# IO_ctrl.net
KiCad netlist of a schematic drawn in Altium Designer
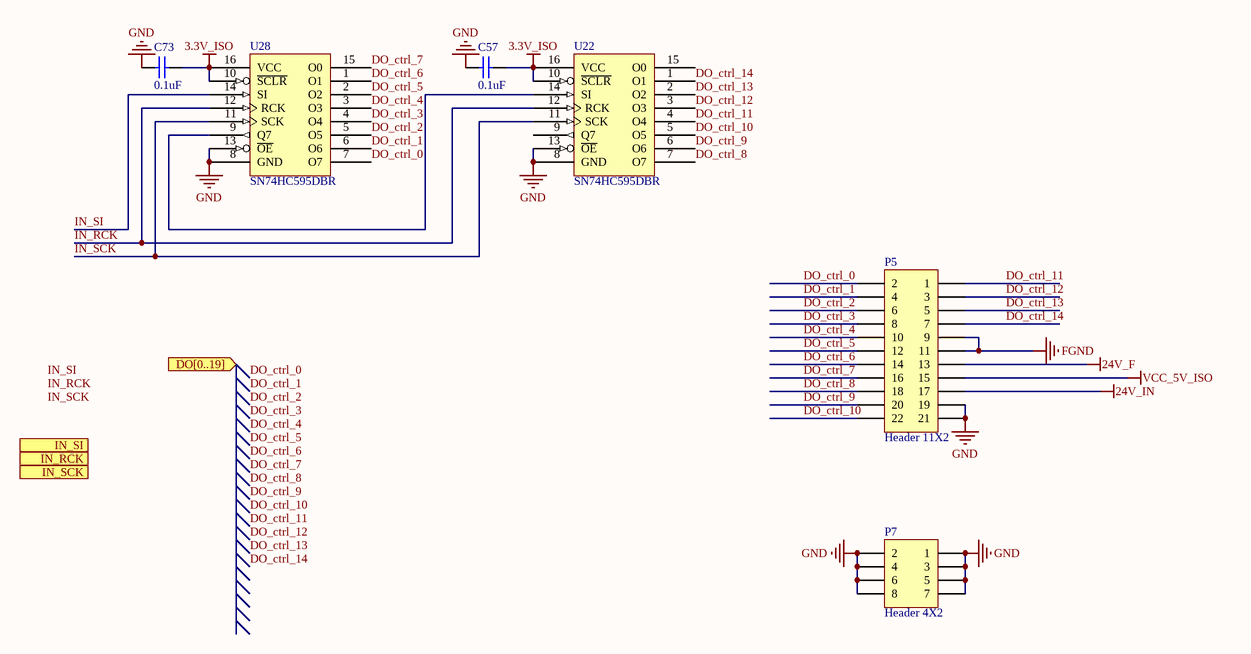
[diagram p0: IO_ctrl.SchDoc]

(export (version "E")
  (design (tool "Eeschema 10.0.6"))
  (components
    (comp (ref "C57")
      (value "0.1uF")
      (footprint "0603C")
      (description "Capacitor")
      (fields (field (name "PUBLISHER") "Altium Limited"))
      (libsource (lib "Miscellaneous Devices") (part "Cap"))
    )
    (comp (ref "C73")
      (value "0.1uF")
      (footprint "0603C")
      (description "Capacitor")
      (fields (field (name "PUBLISHER") "Altium Limited"))
      (libsource (lib "Miscellaneous Devices") (part "Cap"))
    )
    (comp (ref "P5")
      (value "Header 11X2")
      (footprint "HDR2X11")
      (description "Header, 11-Pin, Dual row")
      (fields (field (name "PUBLISHER") "Altium Limited"))
      (libsource (lib "Miscellaneous Connectors") (part "Header 11X2"))
    )
    (comp (ref "P7")
      (value "Header 4X2")
      (footprint "HDR2X4")
      (description "Header, 4-Pin, Dual row")
      (fields (field (name "PUBLISHER") "Altium Limited"))
      (libsource (lib "Miscellaneous Connectors") (part "Header 4X2"))
    )
    (comp (ref "U22") (value "SN74HC595DBR") (footprint "SSOP16") (libsource (lib "DI16") (part "74HC595")))
    (comp (ref "U28") (value "SN74HC595DBR") (footprint "SSOP16") (libsource (lib "DI16") (part "74HC595")))
  )
  (nets
    (net (code "22") (name "/DO_ctrl_0") (class "Default")
      (node (ref "P5") (pin "2") (pinfunction "2_2") (pintype "passive"))
      (node (ref "U28") (pin "7") (pinfunction "O7_7") (pintype "tri_state"))
    )
    (net (code "23") (name "/DO_ctrl_1") (class "Default")
      (node (ref "P5") (pin "4") (pinfunction "4_4") (pintype "passive"))
      (node (ref "U28") (pin "6") (pinfunction "O6_6") (pintype "tri_state"))
    )
    (net (code "24") (name "/DO_ctrl_2") (class "Default")
      (node (ref "P5") (pin "6") (pinfunction "6_6") (pintype "passive"))
      (node (ref "U28") (pin "5") (pinfunction "O5_5") (pintype "tri_state"))
    )
    (net (code "25") (name "/DO_ctrl_3") (class "Default")
      (node (ref "P5") (pin "8") (pinfunction "8_8") (pintype "passive"))
      (node (ref "U28") (pin "4") (pinfunction "O4_4") (pintype "tri_state"))
    )
    (net (code "26") (name "/DO_ctrl_4") (class "Default")
      (node (ref "P5") (pin "10") (pinfunction "10_10") (pintype "passive"))
      (node (ref "U28") (pin "3") (pinfunction "O3_3") (pintype "tri_state"))
    )
    (net (code "27") (name "/DO_ctrl_5") (class "Default")
      (node (ref "P5") (pin "12") (pinfunction "12_12") (pintype "passive"))
      (node (ref "U28") (pin "2") (pinfunction "O2_2") (pintype "tri_state"))
    )
    (net (code "28") (name "/DO_ctrl_6") (class "Default")
      (node (ref "P5") (pin "14") (pinfunction "14_14") (pintype "passive"))
      (node (ref "U28") (pin "1") (pinfunction "O1_1") (pintype "tri_state"))
    )
    (net (code "29") (name "/DO_ctrl_7") (class "Default")
      (node (ref "P5") (pin "16") (pinfunction "16_16") (pintype "passive"))
      (node (ref "U28") (pin "15") (pinfunction "O0_15") (pintype "tri_state"))
    )
    (net (code "30") (name "/DO_ctrl_8") (class "Default")
      (node (ref "P5") (pin "18") (pinfunction "18_18") (pintype "passive"))
      (node (ref "U22") (pin "7") (pinfunction "O7_7") (pintype "tri_state"))
    )
    (net (code "31") (name "/DO_ctrl_9") (class "Default")
      (node (ref "P5") (pin "20") (pinfunction "20_20") (pintype "passive"))
      (node (ref "U22") (pin "6") (pinfunction "O6_6") (pintype "tri_state"))
    )
    (net (code "32") (name "/DO_ctrl_10") (class "Default")
      (node (ref "P5") (pin "22") (pinfunction "22_22") (pintype "passive"))
      (node (ref "U22") (pin "5") (pinfunction "O5_5") (pintype "tri_state"))
    )
    (net (code "33") (name "/DO_ctrl_11") (class "Default")
      (node (ref "P5") (pin "1") (pinfunction "1_1") (pintype "passive"))
      (node (ref "U22") (pin "4") (pinfunction "O4_4") (pintype "tri_state"))
    )
    (net (code "34") (name "/DO_ctrl_12") (class "Default")
      (node (ref "P5") (pin "3") (pinfunction "3_3") (pintype "passive"))
      (node (ref "U22") (pin "3") (pinfunction "O3_3") (pintype "tri_state"))
    )
    (net (code "35") (name "/DO_ctrl_13") (class "Default")
      (node (ref "P5") (pin "5") (pinfunction "5_5") (pintype "passive"))
      (node (ref "U22") (pin "2") (pinfunction "O2_2") (pintype "tri_state"))
    )
    (net (code "36") (name "/DO_ctrl_14") (class "Default")
      (node (ref "P5") (pin "7") (pinfunction "7_7") (pintype "passive"))
      (node (ref "U22") (pin "1") (pinfunction "O1_1") (pintype "tri_state"))
    )
    (net (code "37") (name "/IN_RCK") (class "Default")
      (node (ref "U22") (pin "12") (pinfunction "RCK_12") (pintype "input"))
      (node (ref "U28") (pin "12") (pinfunction "RCK_12") (pintype "input"))
    )
    (net (code "38") (name "/IN_SCK") (class "Default")
      (node (ref "U22") (pin "11") (pinfunction "SCK_11") (pintype "input"))
      (node (ref "U28") (pin "11") (pinfunction "SCK_11") (pintype "input"))
    )
    (net (code "39") (name "/IN_SI") (class "Default")
      (node (ref "U28") (pin "14") (pinfunction "SI_14") (pintype "input"))
    )
    (net (code "40") (name "3.3V_ISO") (class "Default")
      (node (ref "C57") (pin "1") (pinfunction "1_1") (pintype "passive"))
      (node (ref "C73") (pin "1") (pinfunction "1_1") (pintype "passive"))
      (node (ref "U22") (pin "10") (pinfunction "~{SCLR}_10") (pintype "input"))
      (node (ref "U22") (pin "16") (pinfunction "VCC_16") (pintype "power_in"))
      (node (ref "U28") (pin "10") (pinfunction "~{SCLR}_10") (pintype "input"))
      (node (ref "U28") (pin "16") (pinfunction "VCC_16") (pintype "power_in"))
    )
    (net (code "41") (name "24V_F") (class "Default")
      (node (ref "P5") (pin "13") (pinfunction "13_13") (pintype "passive"))
    )
    (net (code "42") (name "24V_IN") (class "Default")
      (node (ref "P5") (pin "17") (pinfunction "17_17") (pintype "passive"))
    )
    (net (code "43") (name "FGND") (class "Default")
      (node (ref "P5") (pin "11") (pinfunction "11_11") (pintype "passive"))
      (node (ref "P5") (pin "9") (pinfunction "9_9") (pintype "passive"))
    )
    (net (code "44") (name "GND") (class "Default")
      (node (ref "C57") (pin "2") (pinfunction "2_2") (pintype "passive"))
      (node (ref "C73") (pin "2") (pinfunction "2_2") (pintype "passive"))
      (node (ref "P5") (pin "19") (pinfunction "19_19") (pintype "passive"))
      (node (ref "P5") (pin "21") (pinfunction "21_21") (pintype "passive"))
      (node (ref "P7") (pin "1") (pinfunction "1_1") (pintype "passive"))
      (node (ref "P7") (pin "2") (pinfunction "2_2") (pintype "passive"))
      (node (ref "P7") (pin "3") (pinfunction "3_3") (pintype "passive"))
      (node (ref "P7") (pin "4") (pinfunction "4_4") (pintype "passive"))
      (node (ref "P7") (pin "5") (pinfunction "5_5") (pintype "passive"))
      (node (ref "P7") (pin "6") (pinfunction "6_6") (pintype "passive"))
      (node (ref "P7") (pin "7") (pinfunction "7_7") (pintype "passive"))
      (node (ref "P7") (pin "8") (pinfunction "8_8") (pintype "passive"))
      (node (ref "U22") (pin "13") (pinfunction "~{OE}_13") (pintype "input"))
      (node (ref "U22") (pin "8") (pinfunction "GND_8") (pintype "power_in"))
      (node (ref "U28") (pin "13") (pinfunction "~{OE}_13") (pintype "input"))
      (node (ref "U28") (pin "8") (pinfunction "GND_8") (pintype "power_in"))
    )
    (net (code "45") (name "Net-(U22-SI)") (class "Default")
      (node (ref "U22") (pin "14") (pinfunction "SI_14") (pintype "input"))
      (node (ref "U28") (pin "9") (pinfunction "Q7_9") (pintype "output"))
    )
    (net (code "46") (name "VCC_5V_ISO") (class "Default")
      (node (ref "P5") (pin "15") (pinfunction "15_15") (pintype "passive"))
    )
    (net (code "47") (name "unconnected-(U22-O0-Pad15)") (class "Default")
      (node (ref "U22") (pin "15") (pinfunction "O0_15") (pintype "tri_state"))
    )
    (net (code "48") (name "unconnected-(U22-Q7-Pad9)") (class "Default")
      (node (ref "U22") (pin "9") (pinfunction "Q7_9") (pintype "output"))
    )
  )
)
